# Sensors.net
KiCad netlist of a schematic drawn in Altium Designer
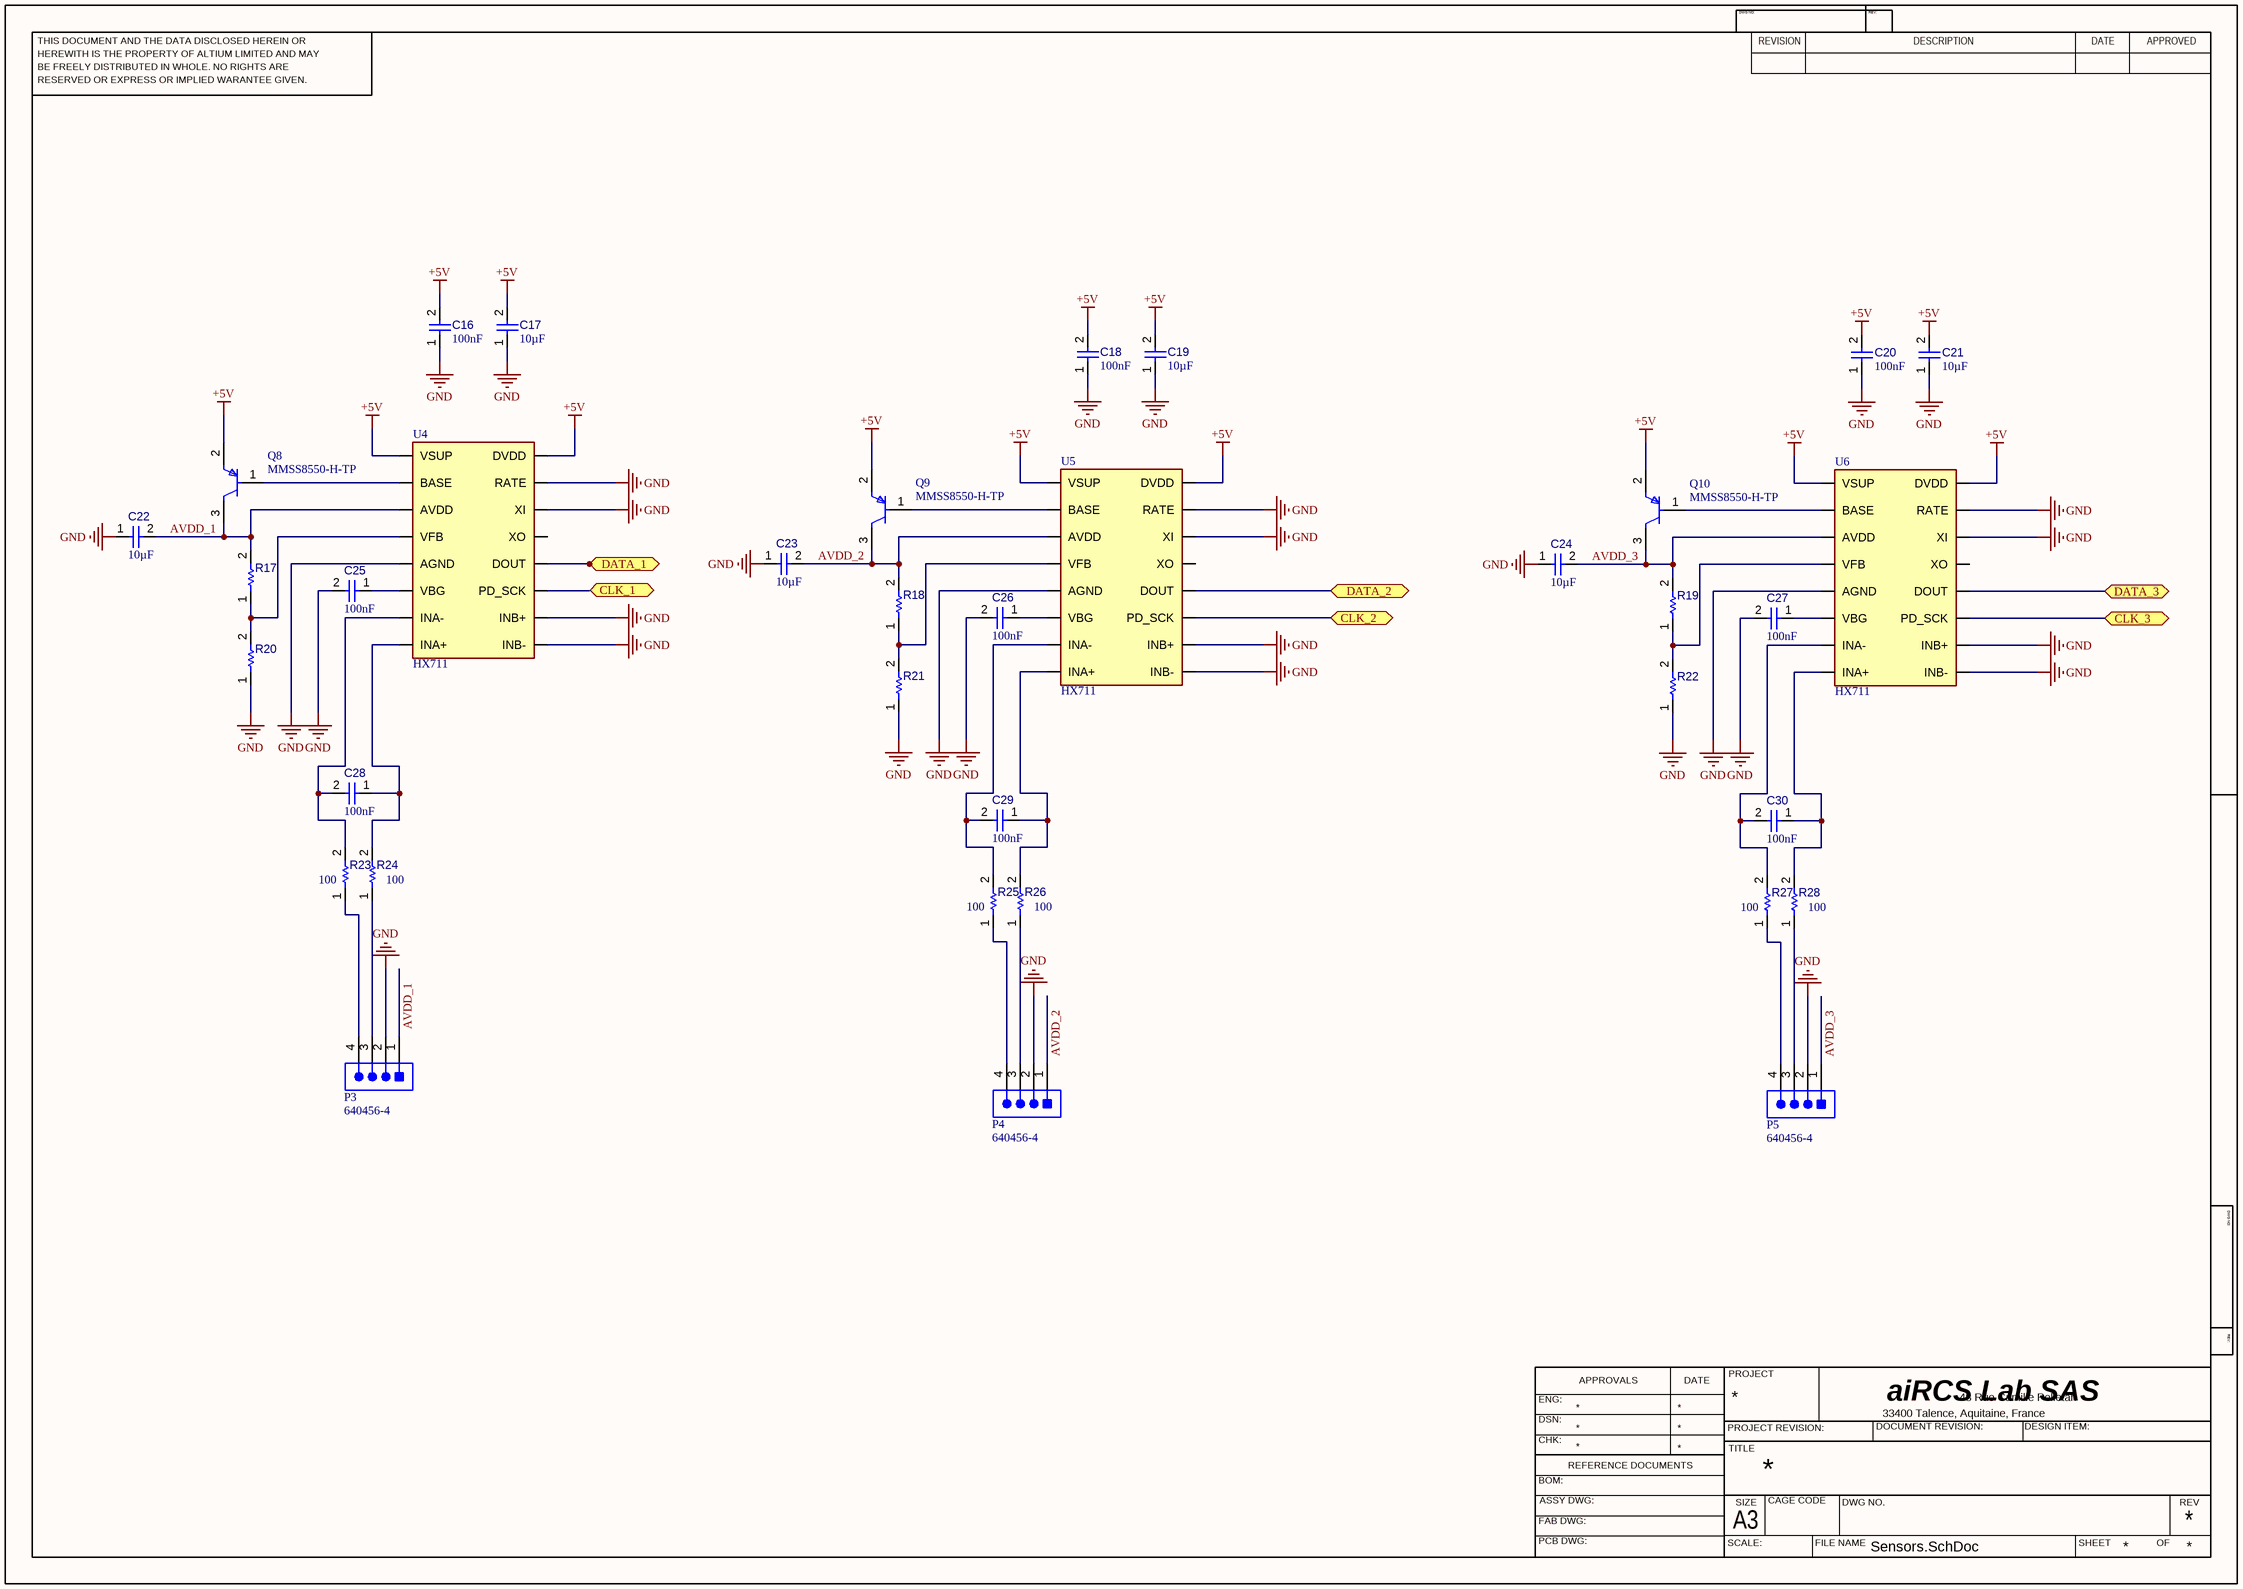
[diagram p0: Sensors.SchDoc]

(export (version "E")
  (design (tool "Eeschema 10.0.6"))
  (components
    (comp (ref "C16")
      (value "100nF")
      (footprint "CAPC0402(1005)60_L")
      (description "Chip Capacitor, 100nF +/-20%, 50V, 0402, Thickness 0.6 mm")
      (fields (field (name "TOLERANCE") "10%") (field (name "Comment") "Capacitor 100nF +/-20% 50V 0402"))
      (libsource (lib "Kariboo") (part "CAP-NP-2"))
    )
    (comp (ref "C17")
      (value "10µF")
      (footprint "CAPC0402(1005)60_L")
      (description "Chip Capacitor, 10µF +/-40%, 6.3V, 0402, Thickness 0.6 mm")
      (fields (field (name "TOLERANCE") "10%") (field (name "Comment") "Capacitor 10µF +/-40% 6.3V 0402"))
      (libsource (lib "Kariboo") (part "CAP-NP-2"))
    )
    (comp (ref "C18")
      (value "100nF")
      (footprint "CAPC0402(1005)60_L")
      (description "Chip Capacitor, 100nF +/-20%, 50V, 0402, Thickness 0.6 mm")
      (fields (field (name "TOLERANCE") "10%") (field (name "Comment") "Capacitor 100nF +/-20% 50V 0402"))
      (libsource (lib "Kariboo") (part "CAP-NP-2"))
    )
    (comp (ref "C19")
      (value "10µF")
      (footprint "CAPC0402(1005)60_L")
      (description "Chip Capacitor, 10µF +/-40%, 6.3V, 0402, Thickness 0.6 mm")
      (fields (field (name "TOLERANCE") "10%") (field (name "Comment") "Capacitor 10µF +/-40% 6.3V 0402"))
      (libsource (lib "Kariboo") (part "CAP-NP-2"))
    )
    (comp (ref "C20")
      (value "100nF")
      (footprint "CAPC0402(1005)60_L")
      (description "Chip Capacitor, 100nF +/-20%, 50V, 0402, Thickness 0.6 mm")
      (fields (field (name "TOLERANCE") "10%") (field (name "Comment") "Capacitor 100nF +/-20% 50V 0402"))
      (libsource (lib "Kariboo") (part "CAP-NP-2"))
    )
    (comp (ref "C21")
      (value "10µF")
      (footprint "CAPC0402(1005)60_L")
      (description "Chip Capacitor, 10µF +/-40%, 6.3V, 0402, Thickness 0.6 mm")
      (fields (field (name "TOLERANCE") "10%") (field (name "Comment") "Capacitor 10µF +/-40% 6.3V 0402"))
      (libsource (lib "Kariboo") (part "CAP-NP-2"))
    )
    (comp (ref "C22")
      (value "10µF")
      (footprint "CAPC0402(1005)60_L")
      (description "Chip Capacitor, 10µF +/-40%, 6.3V, 0402, Thickness 0.6 mm")
      (fields (field (name "TOLERANCE") "10%") (field (name "Comment") "Capacitor 10µF +/-40% 6.3V 0402"))
      (libsource (lib "Kariboo") (part "CAP-NP-2"))
    )
    (comp (ref "C23")
      (value "10µF")
      (footprint "CAPC0402(1005)60_L")
      (description "Chip Capacitor, 10µF +/-40%, 6.3V, 0402, Thickness 0.6 mm")
      (fields (field (name "TOLERANCE") "10%") (field (name "Comment") "Capacitor 10µF +/-40% 6.3V 0402"))
      (libsource (lib "Kariboo") (part "CAP-NP-2"))
    )
    (comp (ref "C24")
      (value "10µF")
      (footprint "CAPC0402(1005)60_L")
      (description "Chip Capacitor, 10µF +/-40%, 6.3V, 0402, Thickness 0.6 mm")
      (fields (field (name "TOLERANCE") "10%") (field (name "Comment") "Capacitor 10µF +/-40% 6.3V 0402"))
      (libsource (lib "Kariboo") (part "CAP-NP-2"))
    )
    (comp (ref "C25")
      (value "100nF")
      (footprint "CAPC0402(1005)60_L")
      (description "Chip Capacitor, 100nF +/-20%, 50V, 0402, Thickness 0.6 mm")
      (fields (field (name "TOLERANCE") "10%") (field (name "Comment") "Capacitor 100nF +/-20% 50V 0402"))
      (libsource (lib "Kariboo") (part "CAP-NP-2"))
    )
    (comp (ref "C26")
      (value "100nF")
      (footprint "CAPC0402(1005)60_L")
      (description "Chip Capacitor, 100nF +/-20%, 50V, 0402, Thickness 0.6 mm")
      (fields (field (name "TOLERANCE") "10%") (field (name "Comment") "Capacitor 100nF +/-20% 50V 0402"))
      (libsource (lib "Kariboo") (part "CAP-NP-2"))
    )
    (comp (ref "C27")
      (value "100nF")
      (footprint "CAPC0402(1005)60_L")
      (description "Chip Capacitor, 100nF +/-20%, 50V, 0402, Thickness 0.6 mm")
      (fields (field (name "TOLERANCE") "10%") (field (name "Comment") "Capacitor 100nF +/-20% 50V 0402"))
      (libsource (lib "Kariboo") (part "CAP-NP-2"))
    )
    (comp (ref "C28")
      (value "100nF")
      (footprint "CAPC0402(1005)60_L")
      (description "Chip Capacitor, 100nF +/-20%, 50V, 0402, Thickness 0.6 mm")
      (fields (field (name "TOLERANCE") "10%") (field (name "Comment") "Capacitor 100nF +/-20% 50V 0402"))
      (libsource (lib "Kariboo") (part "CAP-NP-2"))
    )
    (comp (ref "C29")
      (value "100nF")
      (footprint "CAPC0402(1005)60_L")
      (description "Chip Capacitor, 100nF +/-20%, 50V, 0402, Thickness 0.6 mm")
      (fields (field (name "TOLERANCE") "10%") (field (name "Comment") "Capacitor 100nF +/-20% 50V 0402"))
      (libsource (lib "Kariboo") (part "CAP-NP-2"))
    )
    (comp (ref "C30")
      (value "100nF")
      (footprint "CAPC0402(1005)60_L")
      (description "Chip Capacitor, 100nF +/-20%, 50V, 0402, Thickness 0.6 mm")
      (fields (field (name "TOLERANCE") "10%") (field (name "Comment") "Capacitor 100nF +/-20% 50V 0402"))
      (libsource (lib "Kariboo") (part "CAP-NP-2"))
    )
    (comp (ref "P3")
      (value "640456-4")
      (footprint "TECO-640456-4")
      (description "Male Header, Pitch 2.54 mm, 1 x 4 Position, Height 10.03 mm, Tail Length 3.56 mm, RoHS, Bulk")
      (fields (field (name "MANUFACTURER") "TE Connectivity"))
      (libsource (lib "Altium Content Vault") (part "CN-1P-M-R4"))
    )
    (comp (ref "P4")
      (value "640456-4")
      (footprint "TECO-640456-4")
      (description "Male Header, Pitch 2.54 mm, 1 x 4 Position, Height 10.03 mm, Tail Length 3.56 mm, RoHS, Bulk")
      (fields (field (name "MANUFACTURER") "TE Connectivity"))
      (libsource (lib "Altium Content Vault") (part "CN-1P-M-R4"))
    )
    (comp (ref "P5")
      (value "640456-4")
      (footprint "TECO-640456-4")
      (description "Male Header, Pitch 2.54 mm, 1 x 4 Position, Height 10.03 mm, Tail Length 3.56 mm, RoHS, Bulk")
      (fields (field (name "MANUFACTURER") "TE Connectivity"))
      (libsource (lib "Altium Content Vault") (part "CN-1P-M-R4"))
    )
    (comp (ref "Q8")
      (value "MMSS8550-H-TP")
      (footprint "FP-SOT-23-IPC_B")
      (description "TRANS PNP 25V 1.5A SOT23")
      (libsource (lib "Altium Content Vault") (part "0e8486ed3b47d9c69b8404ba87cf0f7"))
    )
    (comp (ref "Q9")
      (value "MMSS8550-H-TP")
      (footprint "FP-SOT-23-IPC_B")
      (description "TRANS PNP 25V 1.5A SOT23")
      (libsource (lib "Altium Content Vault") (part "0e8486ed3b47d9c69b8404ba87cf0f7"))
    )
    (comp (ref "Q10")
      (value "MMSS8550-H-TP")
      (footprint "FP-SOT-23-IPC_B")
      (description "TRANS PNP 25V 1.5A SOT23")
      (libsource (lib "Altium Content Vault") (part "0e8486ed3b47d9c69b8404ba87cf0f7"))
    )
    (comp (ref "R17")
      (value "RES")
      (footprint "RESC0402(1005)_L")
      (description "Resistor 0402")
      (libsource (lib "Kariboo") (part "0R2J"))
    )
    (comp (ref "R18")
      (value "RES")
      (footprint "RESC0402(1005)_L")
      (description "Resistor 0402")
      (libsource (lib "Kariboo") (part "0R2J"))
    )
    (comp (ref "R19")
      (value "RES")
      (footprint "RESC0402(1005)_L")
      (description "Resistor 0402")
      (libsource (lib "Kariboo") (part "0R2J"))
    )
    (comp (ref "R20")
      (value "RES")
      (footprint "RESC0402(1005)_L")
      (description "Resistor 0402")
      (libsource (lib "Kariboo") (part "0R2J"))
    )
    (comp (ref "R21")
      (value "RES")
      (footprint "RESC0402(1005)_L")
      (description "Resistor 0402")
      (libsource (lib "Kariboo") (part "0R2J"))
    )
    (comp (ref "R22")
      (value "RES")
      (footprint "RESC0402(1005)_L")
      (description "Resistor 0402")
      (libsource (lib "Kariboo") (part "0R2J"))
    )
    (comp (ref "R23") (value "100") (footprint "RESC0402(1005)_L") (libsource (lib "Kariboo") (part "0R2J")))
    (comp (ref "R24") (value "100") (footprint "RESC0402(1005)_L") (libsource (lib "Kariboo") (part "0R2J")))
    (comp (ref "R25") (value "100") (footprint "RESC0402(1005)_L") (libsource (lib "Kariboo") (part "0R2J")))
    (comp (ref "R26") (value "100") (footprint "RESC0402(1005)_L") (libsource (lib "Kariboo") (part "0R2J")))
    (comp (ref "R27") (value "100") (footprint "RESC0402(1005)_L") (libsource (lib "Kariboo") (part "0R2J")))
    (comp (ref "R28") (value "100") (footprint "RESC0402(1005)_L") (libsource (lib "Kariboo") (part "0R2J")))
    (comp (ref "U4")
      (value "HX711")
      (footprint "SOP127P600X180-16N")
      (fields (field (name "MF") "AVIA SEMICONDUCTOR"))
      (libsource (lib "HX711") (part "HX711"))
    )
    (comp (ref "U5")
      (value "HX711")
      (footprint "SOP127P600X180-16N")
      (fields (field (name "MF") "AVIA SEMICONDUCTOR"))
      (libsource (lib "HX711") (part "HX711"))
    )
    (comp (ref "U6")
      (value "HX711")
      (footprint "SOP127P600X180-16N")
      (fields (field (name "MF") "AVIA SEMICONDUCTOR"))
      (libsource (lib "HX711") (part "HX711"))
    )
  )
  (nets
    (net (code "1") (name "+5V") (class "Default")
      (node (ref "C16") (pin "2") (pinfunction "2_2") (pintype "passive"))
      (node (ref "C17") (pin "2") (pinfunction "2_2") (pintype "passive"))
      (node (ref "C18") (pin "2") (pinfunction "2_2") (pintype "passive"))
      (node (ref "C19") (pin "2") (pinfunction "2_2") (pintype "passive"))
      (node (ref "C20") (pin "2") (pinfunction "2_2") (pintype "passive"))
      (node (ref "C21") (pin "2") (pinfunction "2_2") (pintype "passive"))
      (node (ref "Q10") (pin "2") (pinfunction "E_2") (pintype "passive"))
      (node (ref "Q8") (pin "2") (pinfunction "E_2") (pintype "passive"))
      (node (ref "Q9") (pin "2") (pinfunction "E_2") (pintype "passive"))
      (node (ref "U4") (pin "1") (pinfunction "VSUP_1") (pintype "bidirectional"))
      (node (ref "U4") (pin "16") (pinfunction "DVDD_16") (pintype "bidirectional"))
      (node (ref "U5") (pin "1") (pinfunction "VSUP_1") (pintype "bidirectional"))
      (node (ref "U5") (pin "16") (pinfunction "DVDD_16") (pintype "bidirectional"))
      (node (ref "U6") (pin "1") (pinfunction "VSUP_1") (pintype "bidirectional"))
      (node (ref "U6") (pin "16") (pinfunction "DVDD_16") (pintype "bidirectional"))
    )
    (net (code "2") (name "/AVDD_1") (class "Default")
      (node (ref "C22") (pin "2") (pinfunction "2_2") (pintype "passive"))
      (node (ref "P3") (pin "1") (pinfunction "1_1") (pintype "passive"))
      (node (ref "Q8") (pin "3") (pinfunction "C_3") (pintype "passive"))
      (node (ref "R17") (pin "2") (pinfunction "2_2") (pintype "passive"))
      (node (ref "U4") (pin "3") (pinfunction "AVDD_3") (pintype "bidirectional"))
    )
    (net (code "3") (name "/AVDD_2") (class "Default")
      (node (ref "C23") (pin "2") (pinfunction "2_2") (pintype "passive"))
      (node (ref "P4") (pin "1") (pinfunction "1_1") (pintype "passive"))
      (node (ref "Q9") (pin "3") (pinfunction "C_3") (pintype "passive"))
      (node (ref "R18") (pin "2") (pinfunction "2_2") (pintype "passive"))
      (node (ref "U5") (pin "3") (pinfunction "AVDD_3") (pintype "bidirectional"))
    )
    (net (code "4") (name "/AVDD_3") (class "Default")
      (node (ref "C24") (pin "2") (pinfunction "2_2") (pintype "passive"))
      (node (ref "P5") (pin "1") (pinfunction "1_1") (pintype "passive"))
      (node (ref "Q10") (pin "3") (pinfunction "C_3") (pintype "passive"))
      (node (ref "R19") (pin "2") (pinfunction "2_2") (pintype "passive"))
      (node (ref "U6") (pin "3") (pinfunction "AVDD_3") (pintype "bidirectional"))
    )
    (net (code "5") (name "/CLK_1") (class "Default")
      (node (ref "U4") (pin "11") (pinfunction "PD_SCK_11") (pintype "bidirectional"))
    )
    (net (code "6") (name "/CLK_2") (class "Default")
      (node (ref "U5") (pin "11") (pinfunction "PD_SCK_11") (pintype "bidirectional"))
    )
    (net (code "7") (name "/CLK_3") (class "Default")
      (node (ref "U6") (pin "11") (pinfunction "PD_SCK_11") (pintype "bidirectional"))
    )
    (net (code "8") (name "/DATA_1") (class "Default")
      (node (ref "U4") (pin "12") (pinfunction "DOUT_12") (pintype "bidirectional"))
    )
    (net (code "9") (name "/DATA_2") (class "Default")
      (node (ref "U5") (pin "12") (pinfunction "DOUT_12") (pintype "bidirectional"))
    )
    (net (code "10") (name "/DATA_3") (class "Default")
      (node (ref "U6") (pin "12") (pinfunction "DOUT_12") (pintype "bidirectional"))
    )
    (net (code "11") (name "GND") (class "Default")
      (node (ref "C16") (pin "1") (pinfunction "1_1") (pintype "passive"))
      (node (ref "C17") (pin "1") (pinfunction "1_1") (pintype "passive"))
      (node (ref "C18") (pin "1") (pinfunction "1_1") (pintype "passive"))
      (node (ref "C19") (pin "1") (pinfunction "1_1") (pintype "passive"))
      (node (ref "C20") (pin "1") (pinfunction "1_1") (pintype "passive"))
      (node (ref "C21") (pin "1") (pinfunction "1_1") (pintype "passive"))
      (node (ref "C22") (pin "1") (pinfunction "1_1") (pintype "passive"))
      (node (ref "C23") (pin "1") (pinfunction "1_1") (pintype "passive"))
      (node (ref "C24") (pin "1") (pinfunction "1_1") (pintype "passive"))
      (node (ref "C25") (pin "2") (pinfunction "2_2") (pintype "passive"))
      (node (ref "C26") (pin "2") (pinfunction "2_2") (pintype "passive"))
      (node (ref "C27") (pin "2") (pinfunction "2_2") (pintype "passive"))
      (node (ref "P3") (pin "2") (pinfunction "2_2") (pintype "passive"))
      (node (ref "P4") (pin "2") (pinfunction "2_2") (pintype "passive"))
      (node (ref "P5") (pin "2") (pinfunction "2_2") (pintype "passive"))
      (node (ref "R20") (pin "1") (pinfunction "1_1") (pintype "passive"))
      (node (ref "R21") (pin "1") (pinfunction "1_1") (pintype "passive"))
      (node (ref "R22") (pin "1") (pinfunction "1_1") (pintype "passive"))
      (node (ref "U4") (pin "10") (pinfunction "INB+_10") (pintype "bidirectional"))
      (node (ref "U4") (pin "14") (pinfunction "XI_14") (pintype "bidirectional"))
      (node (ref "U4") (pin "15") (pinfunction "RATE_15") (pintype "bidirectional"))
      (node (ref "U4") (pin "5") (pinfunction "AGND_5") (pintype "bidirectional"))
      (node (ref "U4") (pin "9") (pinfunction "INB-_9") (pintype "bidirectional"))
      (node (ref "U5") (pin "10") (pinfunction "INB+_10") (pintype "bidirectional"))
      (node (ref "U5") (pin "14") (pinfunction "XI_14") (pintype "bidirectional"))
      (node (ref "U5") (pin "15") (pinfunction "RATE_15") (pintype "bidirectional"))
      (node (ref "U5") (pin "5") (pinfunction "AGND_5") (pintype "bidirectional"))
      (node (ref "U5") (pin "9") (pinfunction "INB-_9") (pintype "bidirectional"))
      (node (ref "U6") (pin "10") (pinfunction "INB+_10") (pintype "bidirectional"))
      (node (ref "U6") (pin "14") (pinfunction "XI_14") (pintype "bidirectional"))
      (node (ref "U6") (pin "15") (pinfunction "RATE_15") (pintype "bidirectional"))
      (node (ref "U6") (pin "5") (pinfunction "AGND_5") (pintype "bidirectional"))
      (node (ref "U6") (pin "9") (pinfunction "INB-_9") (pintype "bidirectional"))
    )
    (net (code "12") (name "Net-(P3-Pad3)") (class "Default")
      (node (ref "P3") (pin "3") (pinfunction "3_3") (pintype "passive"))
      (node (ref "R24") (pin "1") (pinfunction "1_1") (pintype "passive"))
    )
    (net (code "13") (name "Net-(P3-Pad4)") (class "Default")
      (node (ref "P3") (pin "4") (pinfunction "4_4") (pintype "passive"))
      (node (ref "R23") (pin "1") (pinfunction "1_1") (pintype "passive"))
    )
    (net (code "14") (name "Net-(P4-Pad3)") (class "Default")
      (node (ref "P4") (pin "3") (pinfunction "3_3") (pintype "passive"))
      (node (ref "R26") (pin "1") (pinfunction "1_1") (pintype "passive"))
    )
    (net (code "15") (name "Net-(P4-Pad4)") (class "Default")
      (node (ref "P4") (pin "4") (pinfunction "4_4") (pintype "passive"))
      (node (ref "R25") (pin "1") (pinfunction "1_1") (pintype "passive"))
    )
    (net (code "16") (name "Net-(P5-Pad3)") (class "Default")
      (node (ref "P5") (pin "3") (pinfunction "3_3") (pintype "passive"))
      (node (ref "R28") (pin "1") (pinfunction "1_1") (pintype "passive"))
    )
    (net (code "17") (name "Net-(P5-Pad4)") (class "Default")
      (node (ref "P5") (pin "4") (pinfunction "4_4") (pintype "passive"))
      (node (ref "R27") (pin "1") (pinfunction "1_1") (pintype "passive"))
    )
    (net (code "18") (name "Net-(Q8-B)") (class "Default")
      (node (ref "Q8") (pin "1") (pinfunction "B_1") (pintype "passive"))
      (node (ref "U4") (pin "2") (pinfunction "BASE_2") (pintype "bidirectional"))
    )
    (net (code "19") (name "Net-(Q9-B)") (class "Default")
      (node (ref "Q9") (pin "1") (pinfunction "B_1") (pintype "passive"))
      (node (ref "U5") (pin "2") (pinfunction "BASE_2") (pintype "bidirectional"))
    )
    (net (code "20") (name "Net-(Q10-B)") (class "Default")
      (node (ref "Q10") (pin "1") (pinfunction "B_1") (pintype "passive"))
      (node (ref "U6") (pin "2") (pinfunction "BASE_2") (pintype "bidirectional"))
    )
    (net (code "21") (name "Net-(U4-INA+)") (class "Default")
      (node (ref "C28") (pin "1") (pinfunction "1_1") (pintype "passive"))
      (node (ref "R24") (pin "2") (pinfunction "2_2") (pintype "passive"))
      (node (ref "U4") (pin "8") (pinfunction "INA+_8") (pintype "bidirectional"))
    )
    (net (code "22") (name "Net-(U4-INA-)") (class "Default")
      (node (ref "C28") (pin "2") (pinfunction "2_2") (pintype "passive"))
      (node (ref "R23") (pin "2") (pinfunction "2_2") (pintype "passive"))
      (node (ref "U4") (pin "7") (pinfunction "INA-_7") (pintype "bidirectional"))
    )
    (net (code "23") (name "Net-(U4-VBG)") (class "Default")
      (node (ref "C25") (pin "1") (pinfunction "1_1") (pintype "passive"))
      (node (ref "U4") (pin "6") (pinfunction "VBG_6") (pintype "bidirectional"))
    )
    (net (code "24") (name "Net-(U4-VFB)") (class "Default")
      (node (ref "R17") (pin "1") (pinfunction "1_1") (pintype "passive"))
      (node (ref "R20") (pin "2") (pinfunction "2_2") (pintype "passive"))
      (node (ref "U4") (pin "4") (pinfunction "VFB_4") (pintype "bidirectional"))
    )
    (net (code "25") (name "Net-(U5-INA+)") (class "Default")
      (node (ref "C29") (pin "1") (pinfunction "1_1") (pintype "passive"))
      (node (ref "R26") (pin "2") (pinfunction "2_2") (pintype "passive"))
      (node (ref "U5") (pin "8") (pinfunction "INA+_8") (pintype "bidirectional"))
    )
    (net (code "26") (name "Net-(U5-INA-)") (class "Default")
      (node (ref "C29") (pin "2") (pinfunction "2_2") (pintype "passive"))
      (node (ref "R25") (pin "2") (pinfunction "2_2") (pintype "passive"))
      (node (ref "U5") (pin "7") (pinfunction "INA-_7") (pintype "bidirectional"))
    )
    (net (code "27") (name "Net-(U5-VBG)") (class "Default")
      (node (ref "C26") (pin "1") (pinfunction "1_1") (pintype "passive"))
      (node (ref "U5") (pin "6") (pinfunction "VBG_6") (pintype "bidirectional"))
    )
    (net (code "28") (name "Net-(U5-VFB)") (class "Default")
      (node (ref "R18") (pin "1") (pinfunction "1_1") (pintype "passive"))
      (node (ref "R21") (pin "2") (pinfunction "2_2") (pintype "passive"))
      (node (ref "U5") (pin "4") (pinfunction "VFB_4") (pintype "bidirectional"))
    )
    (net (code "29") (name "Net-(U6-INA+)") (class "Default")
      (node (ref "C30") (pin "1") (pinfunction "1_1") (pintype "passive"))
      (node (ref "R28") (pin "2") (pinfunction "2_2") (pintype "passive"))
      (node (ref "U6") (pin "8") (pinfunction "INA+_8") (pintype "bidirectional"))
    )
    (net (code "30") (name "Net-(U6-INA-)") (class "Default")
      (node (ref "C30") (pin "2") (pinfunction "2_2") (pintype "passive"))
      (node (ref "R27") (pin "2") (pinfunction "2_2") (pintype "passive"))
      (node (ref "U6") (pin "7") (pinfunction "INA-_7") (pintype "bidirectional"))
    )
    (net (code "31") (name "Net-(U6-VBG)") (class "Default")
      (node (ref "C27") (pin "1") (pinfunction "1_1") (pintype "passive"))
      (node (ref "U6") (pin "6") (pinfunction "VBG_6") (pintype "bidirectional"))
    )
    (net (code "32") (name "Net-(U6-VFB)") (class "Default")
      (node (ref "R19") (pin "1") (pinfunction "1_1") (pintype "passive"))
      (node (ref "R22") (pin "2") (pinfunction "2_2") (pintype "passive"))
      (node (ref "U6") (pin "4") (pinfunction "VFB_4") (pintype "bidirectional"))
    )
    (net (code "33") (name "unconnected-(U4-XO-Pad13)") (class "Default")
      (node (ref "U4") (pin "13") (pinfunction "XO_13") (pintype "bidirectional"))
    )
    (net (code "34") (name "unconnected-(U5-XO-Pad13)") (class "Default")
      (node (ref "U5") (pin "13") (pinfunction "XO_13") (pintype "bidirectional"))
    )
    (net (code "35") (name "unconnected-(U6-XO-Pad13)") (class "Default")
      (node (ref "U6") (pin "13") (pinfunction "XO_13") (pintype "bidirectional"))
    )
  )
)
